# Bubble_OCB100.net
KiCad netlist of a schematic drawn in Altium Designer
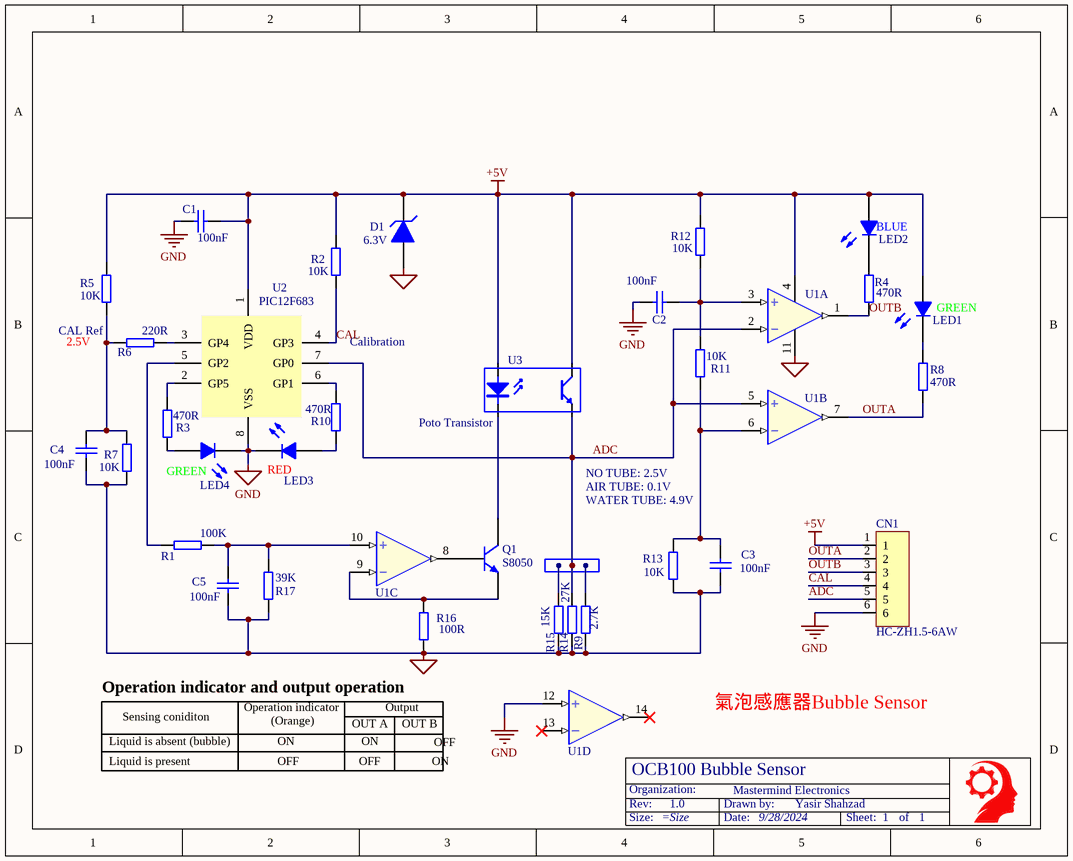
[diagram p0: Bubble_OCB100.SchDoc]

(export (version "E")
  (design (tool "Eeschema 10.0.6"))
  (components
    (comp (ref "*")
      (value "TitleBlock")
      (description "Title Block for Schematic Sheets")
      (libsource (lib "mastermind") (part "TitleBlock"))
    )
    (comp (ref "C1")
      (value "100nF")
      (footprint "C0603-NO")
      (description "Capacitor, X5R, ±10%, 6.3V")
      (fields
        (field (name "PART NUMBER") "C0603-N.C.")
        (field (name "MANUFACTURER") "N.A.")
        (field (name "PUBLISHER") "Nordic Semiconductor")
      )
      (libsource (lib "adafruit") (part "Cap_0603"))
    )
    (comp (ref "C2")
      (value "100nF")
      (footprint "C0603-NO")
      (description "Capacitor, X5R, ±10%, 6.3V")
      (fields
        (field (name "PART NUMBER") "C0603-N.C.")
        (field (name "MANUFACTURER") "N.A.")
        (field (name "PUBLISHER") "Nordic Semiconductor")
      )
      (libsource (lib "adafruit") (part "Cap_0603"))
    )
    (comp (ref "C3")
      (value "100nF")
      (footprint "C0603-NO")
      (description "Capacitor, X5R, ±10%, 6.3V")
      (fields
        (field (name "PART NUMBER") "C0603-N.C.")
        (field (name "MANUFACTURER") "N.A.")
        (field (name "PUBLISHER") "Nordic Semiconductor")
      )
      (libsource (lib "adafruit") (part "Cap_0603"))
    )
    (comp (ref "C4")
      (value "100nF")
      (footprint "C0603-NO")
      (description "Capacitor, X5R, ±10%, 6.3V")
      (fields
        (field (name "PART NUMBER") "C0603-N.C.")
        (field (name "MANUFACTURER") "N.A.")
        (field (name "PUBLISHER") "Nordic Semiconductor")
      )
      (libsource (lib "adafruit") (part "Cap_0603"))
    )
    (comp (ref "C5")
      (value "100nF")
      (footprint "C0603-NO")
      (description "Capacitor, X5R, ±10%, 6.3V")
      (fields
        (field (name "PART NUMBER") "C0603-N.C.")
        (field (name "MANUFACTURER") "N.A.")
        (field (name "PUBLISHER") "Nordic Semiconductor")
      )
      (libsource (lib "adafruit") (part "Cap_0603"))
    )
    (comp (ref "CN1")
      (value "HC-ZH1.5-6AW")
      (footprint "CONN-TH_6P-P1.50_HCTL_C-ZH1.5-6AW")
      (description "1x6P 6P P=1.5mm Wire To Board Connector ROHS")
      (fields (field (name "MANUFACTURER") "HCTL(华灿天禄)"))
      (libsource (lib "Bubble_OCB100") (part "HC-ZH1.5-6AW"))
    )
    (comp (ref "D1")
      (value "D Zener")
      (footprint "SOD-323")
      (description "Zener Diode")
      (fields (field (name "PUBLISHER") "Altium Limited"))
      (libsource (lib "adafruit") (part "Zener"))
    )
    (comp (ref "LED1")
      (value "LED")
      (footprint "CHIPLED_0603 - NO")
      (description "SMD lamp beads")
      (libsource (lib "adafruit") (part "LEDCHIP-LED0603"))
    )
    (comp (ref "LED2")
      (value "LED")
      (footprint "CHIPLED_0603 - NO")
      (description "SMD lamp beads")
      (libsource (lib "adafruit") (part "LEDCHIP-LED0603"))
    )
    (comp (ref "LED3")
      (value "LED")
      (footprint "CHIPLED_0603 - NO")
      (description "SMD lamp beads")
      (libsource (lib "adafruit") (part "LEDCHIP-LED0603"))
    )
    (comp (ref "LED4")
      (value "LED")
      (footprint "CHIPLED_0603 - NO")
      (description "SMD lamp beads")
      (libsource (lib "adafruit") (part "LEDCHIP-LED0603"))
    )
    (comp (ref "P1")
      (value "Header 3")
      (footprint "HDR1X3")
      (description "Header, 3-Pin")
      (fields (field (name "PUBLISHER") "Altium Limited"))
      (libsource (lib "Bubble_OCB100") (part "Header 3"))
    )
    (comp (ref "Q1")
      (value "S8050")
      (footprint "SOT23")
      (description "NPN Bipolar Transistor")
      (fields (field (name "PUBLISHER") "Altium Limited"))
      (libsource (lib "adafruit") (part "NPN"))
    )
    (comp (ref "R1")
      (value "100kΩ")
      (footprint "R0603-NO")
      (description "Resistor, ±1%, 0.100W")
      (fields
        (field (name "PART NUMBER") "R0603-N.C.Ω")
        (field (name "MANUFACTURER") "N.A.")
        (field (name "PUBLISHER") "Nordic Semiconductor")
      )
      (libsource (lib "") (part "Res_0603_2"))
    )
    (comp (ref "R2")
      (value "10kΩ")
      (footprint "R0603-NO")
      (description "Resistor, ±1%, 0.100W")
      (fields
        (field (name "PART NUMBER") "R0603-N.C.Ω")
        (field (name "MANUFACTURER") "N.A.")
        (field (name "PUBLISHER") "Nordic Semiconductor")
      )
      (libsource (lib "") (part "Res_0603_1"))
    )
    (comp (ref "R3")
      (value "470Ω")
      (footprint "R0603-NO")
      (description "Resistor, ±1%, 0.100W")
      (fields
        (field (name "PART NUMBER") "R0603-N.C.Ω")
        (field (name "MANUFACTURER") "N.A.")
        (field (name "PUBLISHER") "Nordic Semiconductor")
      )
      (libsource (lib "adafruit") (part "Res_0603"))
    )
    (comp (ref "R4")
      (value "470Ω")
      (footprint "R0603-NO")
      (description "Resistor, ±1%, 0.100W")
      (fields
        (field (name "PART NUMBER") "R0603-N.C.Ω")
        (field (name "MANUFACTURER") "N.A.")
        (field (name "PUBLISHER") "Nordic Semiconductor")
      )
      (libsource (lib "") (part "Res_0603_1"))
    )
    (comp (ref "R5")
      (value "10kΩ")
      (footprint "R0603-NO")
      (description "Resistor, ±1%, 0.100W")
      (fields
        (field (name "PART NUMBER") "R0603-N.C.Ω")
        (field (name "MANUFACTURER") "N.A.")
        (field (name "PUBLISHER") "Nordic Semiconductor")
      )
      (libsource (lib "adafruit") (part "Res_0603"))
    )
    (comp (ref "R6")
      (value "220Ω")
      (footprint "R0603-NO")
      (description "Resistor, ±1%, 0.100W")
      (fields
        (field (name "PART NUMBER") "R0603-N.C.Ω")
        (field (name "MANUFACTURER") "N.A.")
        (field (name "PUBLISHER") "Nordic Semiconductor")
      )
      (libsource (lib "") (part "Res_0603_2"))
    )
    (comp (ref "R7")
      (value "10kΩ")
      (footprint "R0603-NO")
      (description "Resistor, ±1%, 0.100W")
      (fields
        (field (name "PART NUMBER") "R0603-N.C.Ω")
        (field (name "MANUFACTURER") "N.A.")
        (field (name "PUBLISHER") "Nordic Semiconductor")
      )
      (libsource (lib "") (part "Res_0603_1"))
    )
    (comp (ref "R8")
      (value "470Ω")
      (footprint "R0603-NO")
      (description "Resistor, ±1%, 0.100W")
      (fields
        (field (name "PART NUMBER") "R0603-N.C.Ω")
        (field (name "MANUFACTURER") "N.A.")
        (field (name "PUBLISHER") "Nordic Semiconductor")
      )
      (libsource (lib "") (part "Res_0603_1"))
    )
    (comp (ref "R9")
      (value "2.7kΩ")
      (footprint "R0603-NO")
      (description "Resistor, ±1%, 0.100W")
      (fields
        (field (name "PART NUMBER") "R0603-N.C.Ω")
        (field (name "MANUFACTURER") "N.A.")
        (field (name "PUBLISHER") "Nordic Semiconductor")
      )
      (libsource (lib "adafruit") (part "Res_0603"))
    )
    (comp (ref "R10")
      (value "470Ω")
      (footprint "R0603-NO")
      (description "Resistor, ±1%, 0.100W")
      (fields
        (field (name "PART NUMBER") "R0603-N.C.Ω")
        (field (name "MANUFACTURER") "N.A.")
        (field (name "PUBLISHER") "Nordic Semiconductor")
      )
      (libsource (lib "") (part "Res_0603_1"))
    )
    (comp (ref "R11")
      (value "10kΩ")
      (footprint "R0603-NO")
      (description "Resistor, ±1%, 0.100W")
      (fields
        (field (name "PART NUMBER") "R0603-N.C.Ω")
        (field (name "MANUFACTURER") "N.A.")
        (field (name "PUBLISHER") "Nordic Semiconductor")
      )
      (libsource (lib "") (part "Res_0603_1"))
    )
    (comp (ref "R12")
      (value "10kΩ")
      (footprint "R0603-NO")
      (description "Resistor, ±1%, 0.100W")
      (fields
        (field (name "PART NUMBER") "R0603-N.C.Ω")
        (field (name "MANUFACTURER") "N.A.")
        (field (name "PUBLISHER") "Nordic Semiconductor")
      )
      (libsource (lib "adafruit") (part "Res_0603"))
    )
    (comp (ref "R13")
      (value "10kΩ")
      (footprint "R0603-NO")
      (description "Resistor, ±1%, 0.100W")
      (fields
        (field (name "PART NUMBER") "R0603-N.C.Ω")
        (field (name "MANUFACTURER") "N.A.")
        (field (name "PUBLISHER") "Nordic Semiconductor")
      )
      (libsource (lib "adafruit") (part "Res_0603"))
    )
    (comp (ref "R14")
      (value "27kΩ")
      (footprint "R0603-NO")
      (description "Resistor, ±1%, 0.100W")
      (fields
        (field (name "PART NUMBER") "R0603-N.C.Ω")
        (field (name "MANUFACTURER") "N.A.")
        (field (name "PUBLISHER") "Nordic Semiconductor")
      )
      (libsource (lib "adafruit") (part "Res_0603"))
    )
    (comp (ref "R15")
      (value "15kΩ")
      (footprint "R0603-NO")
      (description "Resistor, ±1%, 0.100W")
      (fields
        (field (name "PART NUMBER") "R0603-N.C.Ω")
        (field (name "MANUFACTURER") "N.A.")
        (field (name "PUBLISHER") "Nordic Semiconductor")
      )
      (libsource (lib "adafruit") (part "Res_0603"))
    )
    (comp (ref "R16")
      (value "100Ω")
      (footprint "R0805-NO")
      (description "Resistor, ±1%, 0.200W")
      (libsource (lib "adafruit") (part "Res_0805"))
    )
    (comp (ref "R17")
      (value "39kΩ")
      (footprint "R0603-NO")
      (description "Resistor, ±1%, 0.100W")
      (fields
        (field (name "PART NUMBER") "R0603-N.C.Ω")
        (field (name "MANUFACTURER") "N.A.")
        (field (name "PUBLISHER") "Nordic Semiconductor")
      )
      (libsource (lib "adafruit") (part "Res_0603"))
    )
    (comp (ref "U1")
      (value "National LM3622 li-ion charger    http://www.ladyada.net/library/eagle")
      (footprint "SOIC127P600X175-14N")
      (description "Four channels 15nA 0.5V/us 1.2MHz SOIC-14 Operational Amplifier ROHS")
      (libsource (lib "mastermind") (part "LM324"))
    )
    (comp (ref "U2")
      (value "PIC12F683")
      (footprint "SOIC-8E")
      (fields (field (name "NAME") "PIC12F683"))
      (libsource (lib "adafruit") (part "PIC12F683"))
    )
    (comp (ref "U3")
      (value "Poto Transistor")
      (footprint "U_Shape_Opto")
      (description "4-Pin Phototransistor Optocoupler")
      (fields (field (name "PUBLISHER") "Altium Limited"))
      (libsource (lib "Bubble_OCB100") (part "U-Shape_Optosens"))
    )
  )
  (nets
    (net (code "1") (name "+5V") (class "Default")
      (node (ref "C1") (pin "1") (pinfunction "1_1") (pintype "passive"))
      (node (ref "CN1") (pin "1") (pinfunction "1_1") (pintype "passive"))
      (node (ref "D1") (pin "K") (pinfunction "K_K") (pintype "passive"))
      (node (ref "LED1") (pin "A") (pinfunction "A_A") (pintype "passive"))
      (node (ref "LED2") (pin "A") (pinfunction "A_A") (pintype "passive"))
      (node (ref "R12") (pin "2") (pinfunction "2_2") (pintype "passive"))
      (node (ref "R2") (pin "1") (pinfunction "1_1") (pintype "passive"))
      (node (ref "R5") (pin "2") (pinfunction "2_2") (pintype "passive"))
      (node (ref "U1") (pin "4") (pinfunction "VCC_4") (pintype "passive"))
      (node (ref "U2") (pin "1") (pinfunction "VDD_1") (pintype "power_in"))
      (node (ref "U3") (pin "1") (pinfunction "A_1") (pintype "passive"))
      (node (ref "U3") (pin "3") (pinfunction "C_3") (pintype "passive"))
    )
    (net (code "2") (name "/ADC") (class "Default")
      (node (ref "CN1") (pin "5") (pinfunction "5_5") (pintype "passive"))
      (node (ref "P1") (pin "2") (pinfunction "2_2") (pintype "passive"))
      (node (ref "R14") (pin "2") (pinfunction "2_2") (pintype "passive"))
      (node (ref "U1") (pin "2") (pinfunction "A-_2") (pintype "input"))
      (node (ref "U1") (pin "5") (pinfunction "B+_5") (pintype "input"))
      (node (ref "U2") (pin "7") (pinfunction "GP0_7") (pintype "passive"))
      (node (ref "U3") (pin "4") (pinfunction "E_4") (pintype "passive"))
    )
    (net (code "3") (name "/CAL") (class "Default")
      (node (ref "CN1") (pin "4") (pinfunction "4_4") (pintype "passive"))
      (node (ref "R2") (pin "2") (pinfunction "2_2") (pintype "passive"))
      (node (ref "U2") (pin "4") (pinfunction "GP3_4") (pintype "power_in"))
    )
    (net (code "4") (name "/OUTA") (class "Default")
      (node (ref "CN1") (pin "2") (pinfunction "2_2") (pintype "passive"))
      (node (ref "R8") (pin "2") (pinfunction "2_2") (pintype "passive"))
      (node (ref "U1") (pin "7") (pinfunction "OB_7") (pintype "output"))
    )
    (net (code "5") (name "/OUTB") (class "Default")
      (node (ref "CN1") (pin "3") (pinfunction "3_3") (pintype "passive"))
      (node (ref "R4") (pin "2") (pinfunction "2_2") (pintype "passive"))
      (node (ref "U1") (pin "1") (pinfunction "OA_1") (pintype "output"))
    )
    (net (code "6") (name "GND") (class "Default")
      (node (ref "C1") (pin "2") (pinfunction "2_2") (pintype "passive"))
      (node (ref "C2") (pin "2") (pinfunction "2_2") (pintype "passive"))
      (node (ref "C3") (pin "1") (pinfunction "1_1") (pintype "passive"))
      (node (ref "C4") (pin "2") (pinfunction "2_2") (pintype "passive"))
      (node (ref "C5") (pin "1") (pinfunction "1_1") (pintype "passive"))
      (node (ref "CN1") (pin "6") (pinfunction "6_6") (pintype "passive"))
      (node (ref "D1") (pin "A") (pinfunction "A_A") (pintype "passive"))
      (node (ref "LED3") (pin "C") (pinfunction "K_C") (pintype "passive"))
      (node (ref "LED4") (pin "C") (pinfunction "K_C") (pintype "passive"))
      (node (ref "R13") (pin "1") (pinfunction "1_1") (pintype "passive"))
      (node (ref "R14") (pin "1") (pinfunction "1_1") (pintype "passive"))
      (node (ref "R15") (pin "1") (pinfunction "1_1") (pintype "passive"))
      (node (ref "R16") (pin "1") (pinfunction "1_1") (pintype "passive"))
      (node (ref "R17") (pin "1") (pinfunction "1_1") (pintype "passive"))
      (node (ref "R7") (pin "2") (pinfunction "2_2") (pintype "passive"))
      (node (ref "R9") (pin "1") (pinfunction "1_1") (pintype "passive"))
      (node (ref "U1") (pin "11") (pinfunction "GND_11") (pintype "passive"))
      (node (ref "U1") (pin "12") (pinfunction "D+_12") (pintype "input"))
      (node (ref "U2") (pin "8") (pinfunction "VSS_8") (pintype "passive"))
    )
    (net (code "7") (name "Net-(C4-Pad1)") (class "Default")
      (node (ref "C4") (pin "1") (pinfunction "1_1") (pintype "passive"))
      (node (ref "R5") (pin "1") (pinfunction "1_1") (pintype "passive"))
      (node (ref "R6") (pin "1") (pinfunction "1_1") (pintype "passive"))
      (node (ref "R7") (pin "1") (pinfunction "1_1") (pintype "passive"))
    )
    (net (code "8") (name "Net-(LED1-K)") (class "Default")
      (node (ref "LED1") (pin "C") (pinfunction "K_C") (pintype "passive"))
      (node (ref "R8") (pin "1") (pinfunction "1_1") (pintype "passive"))
    )
    (net (code "9") (name "Net-(LED2-K)") (class "Default")
      (node (ref "LED2") (pin "C") (pinfunction "K_C") (pintype "passive"))
      (node (ref "R4") (pin "1") (pinfunction "1_1") (pintype "passive"))
    )
    (net (code "10") (name "Net-(LED3-PadA)") (class "Default")
      (node (ref "LED3") (pin "A") (pinfunction "A_A") (pintype "passive"))
      (node (ref "R10") (pin "2") (pinfunction "2_2") (pintype "passive"))
    )
    (net (code "11") (name "Net-(LED4-PadA)") (class "Default")
      (node (ref "LED4") (pin "A") (pinfunction "A_A") (pintype "passive"))
      (node (ref "R3") (pin "1") (pinfunction "1_1") (pintype "passive"))
    )
    (net (code "12") (name "Net-(P1-Pad1)") (class "Default")
      (node (ref "P1") (pin "1") (pinfunction "1_1") (pintype "passive"))
      (node (ref "R9") (pin "2") (pinfunction "2_2") (pintype "passive"))
    )
    (net (code "13") (name "Net-(P1-Pad3)") (class "Default")
      (node (ref "P1") (pin "3") (pinfunction "3_3") (pintype "passive"))
      (node (ref "R15") (pin "2") (pinfunction "2_2") (pintype "passive"))
    )
    (net (code "14") (name "Net-(Q1-B)") (class "Default")
      (node (ref "Q1") (pin "1") (pinfunction "B_1") (pintype "passive"))
      (node (ref "U1") (pin "8") (pinfunction "OC_8") (pintype "output"))
    )
    (net (code "15") (name "Net-(Q1-C)") (class "Default")
      (node (ref "Q1") (pin "3") (pinfunction "C_3") (pintype "passive"))
      (node (ref "U3") (pin "2") (pinfunction "K_2") (pintype "passive"))
    )
    (net (code "16") (name "Net-(Q1-E)") (class "Default")
      (node (ref "Q1") (pin "2") (pinfunction "E_2") (pintype "passive"))
      (node (ref "R16") (pin "2") (pinfunction "2_2") (pintype "passive"))
      (node (ref "U1") (pin "9") (pinfunction "C-_9") (pintype "input"))
    )
    (net (code "17") (name "Net-(U1A-A+)") (class "Default")
      (node (ref "C2") (pin "1") (pinfunction "1_1") (pintype "passive"))
      (node (ref "R11") (pin "1") (pinfunction "1_1") (pintype "passive"))
      (node (ref "R12") (pin "1") (pinfunction "1_1") (pintype "passive"))
      (node (ref "U1") (pin "3") (pinfunction "A+_3") (pintype "input"))
    )
    (net (code "18") (name "Net-(U1B-B-)") (class "Default")
      (node (ref "C3") (pin "2") (pinfunction "2_2") (pintype "passive"))
      (node (ref "R11") (pin "2") (pinfunction "2_2") (pintype "passive"))
      (node (ref "R13") (pin "2") (pinfunction "2_2") (pintype "passive"))
      (node (ref "U1") (pin "6") (pinfunction "B-_6") (pintype "input"))
    )
    (net (code "19") (name "Net-(U1C-C+)") (class "Default")
      (node (ref "C5") (pin "2") (pinfunction "2_2") (pintype "passive"))
      (node (ref "R1") (pin "2") (pinfunction "2_2") (pintype "passive"))
      (node (ref "R17") (pin "2") (pinfunction "2_2") (pintype "passive"))
      (node (ref "U1") (pin "10") (pinfunction "C+_10") (pintype "input"))
    )
    (net (code "20") (name "Net-(U2-GP1)") (class "Default")
      (node (ref "R10") (pin "1") (pinfunction "1_1") (pintype "passive"))
      (node (ref "U2") (pin "6") (pinfunction "GP1_6") (pintype "passive"))
    )
    (net (code "21") (name "Net-(U2-GP2)") (class "Default")
      (node (ref "R1") (pin "1") (pinfunction "1_1") (pintype "passive"))
      (node (ref "U2") (pin "5") (pinfunction "GP2_5") (pintype "passive"))
    )
    (net (code "22") (name "Net-(U2-GP4)") (class "Default")
      (node (ref "R6") (pin "2") (pinfunction "2_2") (pintype "passive"))
      (node (ref "U2") (pin "3") (pinfunction "GP4_3") (pintype "passive"))
    )
    (net (code "23") (name "Net-(U2-GP5)") (class "Default")
      (node (ref "R3") (pin "2") (pinfunction "2_2") (pintype "passive"))
      (node (ref "U2") (pin "2") (pinfunction "GP5_2") (pintype "passive"))
    )
    (net (code "24") (name "unconnected-(U1D-D--Pad13)") (class "Default")
      (node (ref "U1") (pin "13") (pinfunction "D-_13") (pintype "input+no_connect"))
    )
    (net (code "25") (name "unconnected-(U1D-OD-Pad14)") (class "Default")
      (node (ref "U1") (pin "14") (pinfunction "OD_14") (pintype "output+no_connect"))
    )
  )
)
